# Temperature_Sensors.net
KiCad netlist of a schematic drawn in Altium Designer
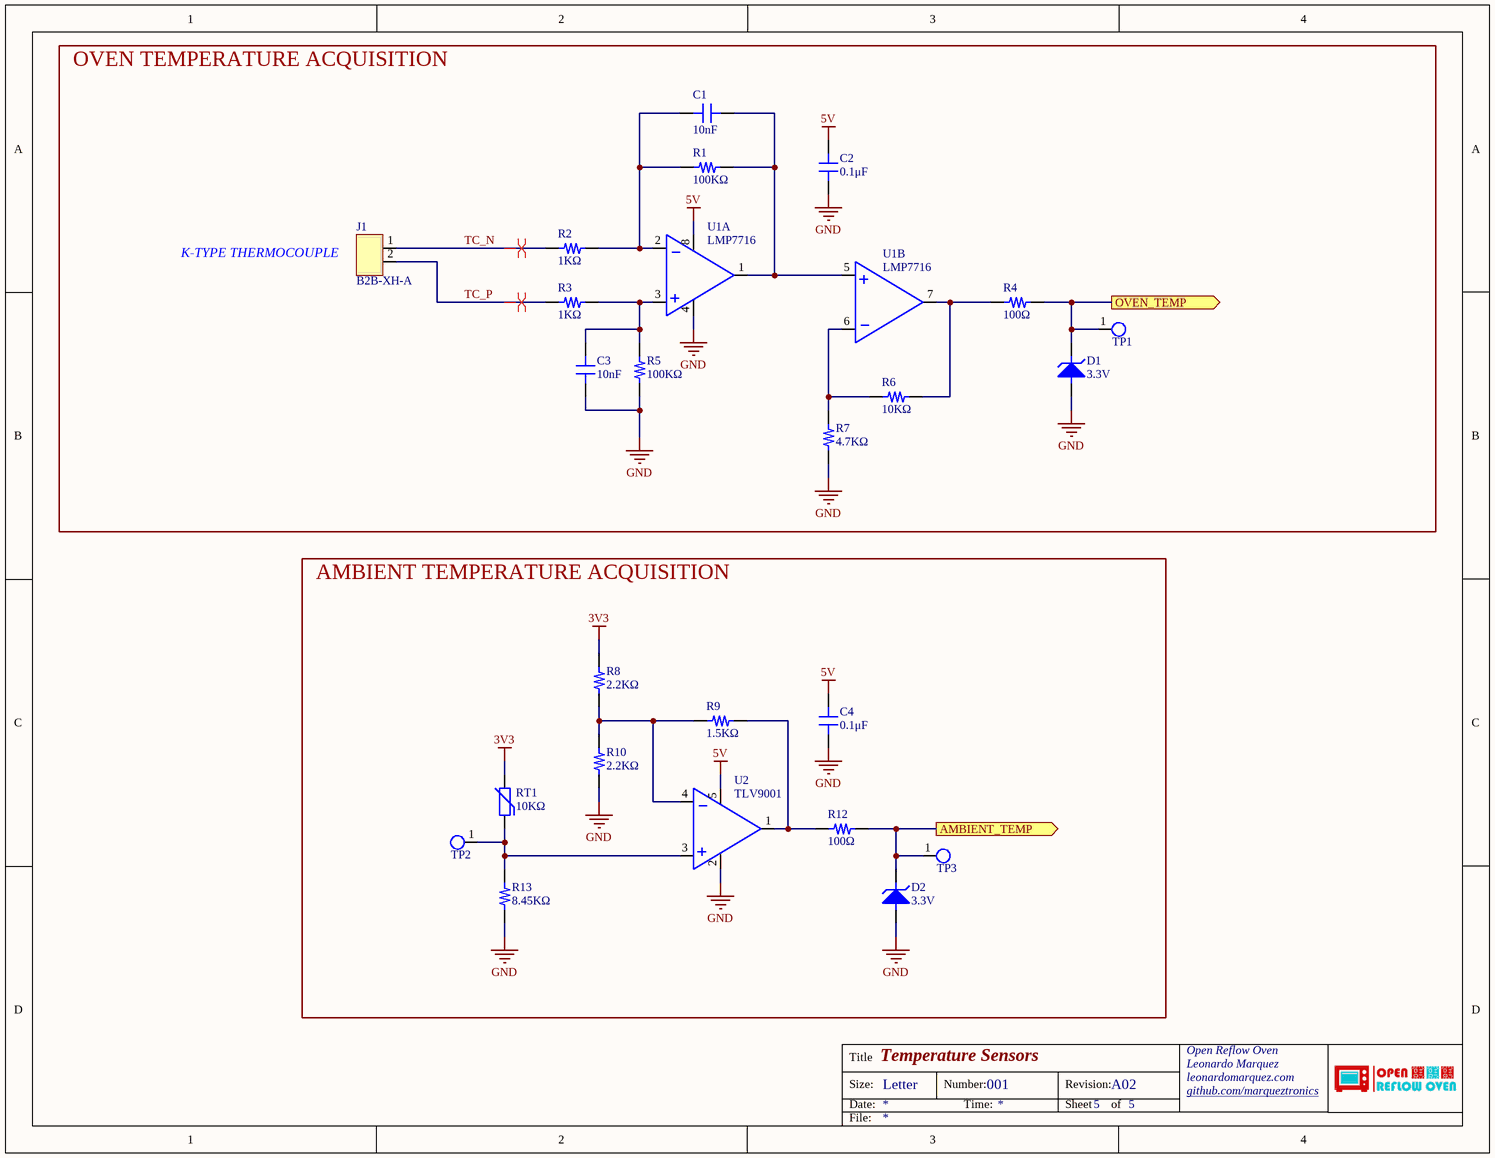
[diagram p0: Temperature Sensors.SchDoc]

(export (version "E")
  (design (tool "Eeschema 10.0.6"))
  (components
    (comp (ref "C1")
      (value "10nF")
      (footprint "C0603")
      (description "50V 10nF X7R ±10% 0603 Multilayer Ceramic Capacitors MLCC - SMD/SMT ROHS")
      (fields
        (field (name "MANUFACTURER") "Samsung Electro-Mechanics")
        (field (name "MANUFACTURER PART NUMBER") "CL10B103KB8NNNC")
      )
      (libsource (lib "REFLOW_CONTROLLER") (part "C-10NF-50V-X7R-C0603"))
    )
    (comp (ref "C2")
      (value "0.1μF")
      (footprint "C0603")
      (description "50V 100nF X7R ±10% 0603 Multilayer Ceramic Capacitors MLCC - SMD/SMT ROHS")
      (fields
        (field (name "MANUFACTURER") "Samsung Electro-Mechanics")
        (field (name "MANUFACTURER PART NUMBER") "CL10B104KB8NNNC")
      )
      (libsource (lib "REFLOW_CONTROLLER") (part "C-0.1UF-50V-X7R-C0603"))
    )
    (comp (ref "C3")
      (value "10nF")
      (footprint "C0603")
      (description "50V 10nF X7R ±10% 0603 Multilayer Ceramic Capacitors MLCC - SMD/SMT ROHS")
      (fields
        (field (name "MANUFACTURER") "Samsung Electro-Mechanics")
        (field (name "MANUFACTURER PART NUMBER") "CL10B103KB8NNNC")
      )
      (libsource (lib "REFLOW_CONTROLLER") (part "C-10NF-50V-X7R-C0603"))
    )
    (comp (ref "C4")
      (value "0.1μF")
      (footprint "C0603")
      (description "50V 100nF X7R ±10% 0603 Multilayer Ceramic Capacitors MLCC - SMD/SMT ROHS")
      (fields
        (field (name "MANUFACTURER") "Samsung Electro-Mechanics")
        (field (name "MANUFACTURER PART NUMBER") "CL10B104KB8NNNC")
      )
      (libsource (lib "REFLOW_CONTROLLER") (part "C-0.1UF-50V-X7R-C0603"))
    )
    (comp (ref "D1")
      (value "3.3V")
      (footprint "SOD-323")
      (description "Single 3.32V~3.53V 400mW 3.3V SOD-323 Zener Diodes ROHS")
      (fields
        (field (name "MANUFACTURER") "Nexperia")
        (field (name "MANUFACTURER PART NUMBER") "PDZ3.3B,115")
      )
      (libsource (lib "REFLOW_CONTROLLER") (part "D-ZENER-3.3V-SOD-323"))
    )
    (comp (ref "D2")
      (value "3.3V")
      (footprint "SOD-323")
      (description "Single 3.32V~3.53V 400mW 3.3V SOD-323 Zener Diodes ROHS")
      (fields
        (field (name "MANUFACTURER") "Nexperia")
        (field (name "MANUFACTURER PART NUMBER") "PDZ3.3B,115")
      )
      (libsource (lib "REFLOW_CONTROLLER") (part "D-ZENER-3.3V-SOD-323"))
    )
    (comp (ref "J1")
      (value "B2B-XH-A")
      (footprint "B2B-XH-A")
      (description "1x2P 2P XH 1 2.5mm 2 Brass Plugin,P=2.5mm Wire To Board Connector ROHS")
      (fields
        (field (name "MANUFACTURER") "JST")
        (field (name "MANUFACTURER PART NUMBER") "B2B-XH-A(LF)(SN)")
      )
      (libsource (lib "REFLOW_CONTROLLER") (part "J-2P-2.5MM-B2B-XH-A"))
    )
    (comp (ref "R1")
      (value "100KΩ")
      (footprint "R0603")
      (description "100mW Thick Film Resistors 75V ±100ppm/℃ ±1% 100kΩ 0603 Chip Resistor - Surface Mount ROHS")
      (fields
        (field (name "MANUFACTURER") "Yageo")
        (field (name "MANUFACTURER PART NUMBER") "RC0603FR-07100KL")
      )
      (libsource (lib "REFLOW_CONTROLLER") (part "R-100K-1/10W-R0603"))
    )
    (comp (ref "R2")
      (value "1KΩ")
      (footprint "R0603")
      (description "100mW Thick Film Resistors 75V ±100ppm/℃ ±1% 1kΩ 0603 Chip Resistor - Surface Mount ROHS")
      (fields
        (field (name "MANUFACTURER") "Yageo")
        (field (name "MANUFACTURER PART NUMBER") "RC0603FR-071KL")
      )
      (libsource (lib "REFLOW_CONTROLLER") (part "R-1K-1/10W-R0603"))
    )
    (comp (ref "R3")
      (value "1KΩ")
      (footprint "R0603")
      (description "100mW Thick Film Resistors 75V ±100ppm/℃ ±1% 1kΩ 0603 Chip Resistor - Surface Mount ROHS")
      (fields
        (field (name "MANUFACTURER") "Yageo")
        (field (name "MANUFACTURER PART NUMBER") "RC0603FR-071KL")
      )
      (libsource (lib "REFLOW_CONTROLLER") (part "R-1K-1/10W-R0603"))
    )
    (comp (ref "R4")
      (value "100Ω")
      (footprint "R0603")
      (description "100mW Thick Film Resistors 75V ±100ppm/℃ ±1% 100Ω 0603 Chip Resistor - Surface Mount ROHS")
      (fields
        (field (name "MANUFACTURER") "Yageo")
        (field (name "MANUFACTURER PART NUMBER") "RC0603FR-07100RL")
      )
      (libsource (lib "REFLOW_CONTROLLER") (part "R-100-1/10W-R0603"))
    )
    (comp (ref "R5")
      (value "100KΩ")
      (footprint "R0603")
      (description "100mW Thick Film Resistors 75V ±100ppm/℃ ±1% 100kΩ 0603 Chip Resistor - Surface Mount ROHS")
      (fields
        (field (name "MANUFACTURER") "Yageo")
        (field (name "MANUFACTURER PART NUMBER") "RC0603FR-07100KL")
      )
      (libsource (lib "REFLOW_CONTROLLER") (part "R-100K-1/10W-R0603"))
    )
    (comp (ref "R6")
      (value "10KΩ")
      (footprint "R0603")
      (description "100mW Thick Film Resistors 75V ±100ppm/℃ ±1% 10kΩ 0603 Chip Resistor - Surface Mount ROHS")
      (fields
        (field (name "MANUFACTURER") "Yageo")
        (field (name "MANUFACTURER PART NUMBER") "RC0603FR-0710KL")
      )
      (libsource (lib "REFLOW_CONTROLLER") (part "R-10K-1/10W-R0603"))
    )
    (comp (ref "R7")
      (value "4.7KΩ")
      (footprint "R0603")
      (description "100mW Thick Film Resistors 75V ±100ppm/℃ ±1% 4.7kΩ 0603 Chip Resistor - Surface Mount ROHS")
      (fields
        (field (name "MANUFACTURER") "Yageo")
        (field (name "MANUFACTURER PART NUMBER") "RC0603FR-074K7L")
      )
      (libsource (lib "REFLOW_CONTROLLER") (part "R-4.7K-1/10W-R0603"))
    )
    (comp (ref "R8")
      (value "2.2KΩ")
      (footprint "R0603")
      (description "100mW Thick Film Resistors 75V ±100ppm/℃ ±1% 2.2kΩ 0603 Chip Resistor - Surface Mount ROHS")
      (fields
        (field (name "MANUFACTURER") "Yageo")
        (field (name "MANUFACTURER PART NUMBER") "RC0603FR-072K2L")
      )
      (libsource (lib "REFLOW_CONTROLLER") (part "R-2.2K-1/10W-R0603"))
    )
    (comp (ref "R9")
      (value "1.5KΩ")
      (footprint "R0603")
      (description "100mW Thick Film Resistors 75V ±100ppm/℃ ±1% 1.5kΩ 0603 Chip Resistor - Surface Mount ROHS")
      (fields
        (field (name "MANUFACTURER") "Yageo")
        (field (name "MANUFACTURER PART NUMBER") "RC0603FR-071K5L")
      )
      (libsource (lib "REFLOW_CONTROLLER") (part "R-1.5K-1/10W-R0603"))
    )
    (comp (ref "R10")
      (value "2.2KΩ")
      (footprint "R0603")
      (description "100mW Thick Film Resistors 75V ±100ppm/℃ ±1% 2.2kΩ 0603 Chip Resistor - Surface Mount ROHS")
      (fields
        (field (name "MANUFACTURER") "Yageo")
        (field (name "MANUFACTURER PART NUMBER") "RC0603FR-072K2L")
      )
      (libsource (lib "REFLOW_CONTROLLER") (part "R-2.2K-1/10W-R0603"))
    )
    (comp (ref "R12")
      (value "100Ω")
      (footprint "R0603")
      (description "100mW Thick Film Resistors 75V ±100ppm/℃ ±1% 100Ω 0603 Chip Resistor - Surface Mount ROHS")
      (fields
        (field (name "MANUFACTURER") "Yageo")
        (field (name "MANUFACTURER PART NUMBER") "RC0603FR-07100RL")
      )
      (libsource (lib "REFLOW_CONTROLLER") (part "R-100-1/10W-R0603"))
    )
    (comp (ref "R13")
      (value "8.45KΩ")
      (footprint "R0603")
      (description "100mW Thick Film Resistors 75V ±100ppm/℃ ±1% 8.45kΩ 0603 Chip Resistor - Surface Mount ROHS")
      (fields
        (field (name "MANUFACTURER") "Yageo")
        (field (name "MANUFACTURER PART NUMBER") "RC0603FR-078K45L")
      )
      (libsource (lib "REFLOW_CONTROLLER") (part "R-8.45K-1/10W-R0603"))
    )
    (comp (ref "RT1")
      (value "10KΩ")
      (footprint "RT0603")
      (description "10kΩ 330uA 100mW ±1% 3950K ±1% 0603 NTC Thermistors ROHS")
      (fields
        (field (name "MANUFACTURER") "Sunlord")
        (field (name "MANUFACTURER PART NUMBER") "SDNT1608X103F3950FTF")
      )
      (libsource (lib "REFLOW_CONTROLLER") (part "RT-10K-NTC-RT0603"))
    )
    (comp (ref "TP1")
      (value "TP-1MM-ROUND")
      (footprint "TP-1MM-ROUND")
      (description "Round Test Point 1mm Dia")
      (libsource (lib "REFLOW_CONTROLLER") (part "TP-1MM-ROUND"))
    )
    (comp (ref "TP2")
      (value "TP-1MM-ROUND")
      (footprint "TP-1MM-ROUND")
      (description "Round Test Point 1mm Dia")
      (libsource (lib "REFLOW_CONTROLLER") (part "TP-1MM-ROUND"))
    )
    (comp (ref "TP3")
      (value "TP-1MM-ROUND")
      (footprint "TP-1MM-ROUND")
      (description "Round Test Point 1mm Dia")
      (libsource (lib "REFLOW_CONTROLLER") (part "TP-1MM-ROUND"))
    )
    (comp (ref "U1")
      (value "LMP7716")
      (footprint "VSSOP-8")
      (description "17MHz 0.1pA Dual VSSOP-8 Precision OpAmps ROHS")
      (fields
        (field (name "MANUFACTURER") "Texas Instruments")
        (field (name "MANUFACTURER PART NUMBER") "LMP7716MM/NOPB")
      )
      (libsource (lib "REFLOW_CONTROLLER") (part "U-LMP7716MM/NOPB-VSSOP-8"))
    )
    (comp (ref "U2")
      (value "TLV9001")
      (footprint "SOT-23-5")
      (description "5pA Single 1MHz SOT-23-5 Operational Amplifier ROHS")
      (fields
        (field (name "MANUFACTURER") "Texas Instruments")
        (field (name "MANUFACTURER PART NUMBER") "TLV9001IDBVR")
      )
      (libsource (lib "REFLOW_CONTROLLER") (part "U-TLV9001IDBVR-SOT-23-5"))
    )
  )
  (nets
    (net (code "1") (name "/AMBIENT_TEMP") (class "Default")
      (node (ref "D2") (pin "K") (pinfunction "K_K") (pintype "passive"))
      (node (ref "R12") (pin "2") (pinfunction "2_2") (pintype "passive"))
      (node (ref "TP3") (pin "1") (pinfunction "1_1") (pintype "passive"))
    )
    (net (code "2") (name "/OVEN_TEMP") (class "Default")
      (node (ref "D1") (pin "K") (pinfunction "K_K") (pintype "passive"))
      (node (ref "R4") (pin "2") (pinfunction "2_2") (pintype "passive"))
      (node (ref "TP1") (pin "1") (pinfunction "1_1") (pintype "passive"))
    )
    (net (code "3") (name "/TC_N") (class "Default")
      (node (ref "J1") (pin "1") (pinfunction "1_1") (pintype "passive"))
      (node (ref "R2") (pin "1") (pinfunction "1_1") (pintype "passive"))
    )
    (net (code "4") (name "/TC_P") (class "Default")
      (node (ref "J1") (pin "2") (pinfunction "2_2") (pintype "passive"))
      (node (ref "R3") (pin "1") (pinfunction "1_1") (pintype "passive"))
    )
    (net (code "5") (name "3V3") (class "Default")
      (node (ref "R8") (pin "2") (pinfunction "2_2") (pintype "passive"))
      (node (ref "RT1") (pin "2") (pinfunction "2_2") (pintype "passive"))
    )
    (net (code "6") (name "5V") (class "Default")
      (node (ref "C2") (pin "2") (pinfunction "2_2") (pintype "passive"))
      (node (ref "C4") (pin "2") (pinfunction "2_2") (pintype "passive"))
      (node (ref "U1") (pin "8") (pinfunction "V+_8") (pintype "passive"))
      (node (ref "U2") (pin "5") (pinfunction "V+_5") (pintype "passive"))
    )
    (net (code "7") (name "GND") (class "Default")
      (node (ref "C2") (pin "1") (pinfunction "1_1") (pintype "passive"))
      (node (ref "C3") (pin "1") (pinfunction "1_1") (pintype "passive"))
      (node (ref "C4") (pin "1") (pinfunction "1_1") (pintype "passive"))
      (node (ref "D1") (pin "A") (pinfunction "A_A") (pintype "passive"))
      (node (ref "D2") (pin "A") (pinfunction "A_A") (pintype "passive"))
      (node (ref "R10") (pin "1") (pinfunction "1_1") (pintype "passive"))
      (node (ref "R13") (pin "1") (pinfunction "1_1") (pintype "passive"))
      (node (ref "R5") (pin "1") (pinfunction "1_1") (pintype "passive"))
      (node (ref "R7") (pin "1") (pinfunction "1_1") (pintype "passive"))
      (node (ref "U1") (pin "4") (pinfunction "V-_4") (pintype "passive"))
      (node (ref "U2") (pin "2") (pinfunction "V-_2") (pintype "passive"))
    )
    (net (code "8") (name "Net-(U1A-+IN_A)") (class "Default")
      (node (ref "C3") (pin "2") (pinfunction "2_2") (pintype "passive"))
      (node (ref "R3") (pin "2") (pinfunction "2_2") (pintype "passive"))
      (node (ref "R5") (pin "2") (pinfunction "2_2") (pintype "passive"))
      (node (ref "U1") (pin "3") (pinfunction "+IN_A_3") (pintype "passive"))
    )
    (net (code "9") (name "Net-(U1A--IN_A)") (class "Default")
      (node (ref "C1") (pin "1") (pinfunction "1_1") (pintype "passive"))
      (node (ref "R1") (pin "2") (pinfunction "2_2") (pintype "passive"))
      (node (ref "R2") (pin "2") (pinfunction "2_2") (pintype "passive"))
      (node (ref "U1") (pin "2") (pinfunction "-IN_A_2") (pintype "passive"))
    )
    (net (code "10") (name "Net-(U1A-OUT_A)") (class "Default")
      (node (ref "C1") (pin "2") (pinfunction "2_2") (pintype "passive"))
      (node (ref "R1") (pin "1") (pinfunction "1_1") (pintype "passive"))
      (node (ref "U1") (pin "1") (pinfunction "OUT_A_1") (pintype "passive"))
      (node (ref "U1") (pin "5") (pinfunction "+IN_B_5") (pintype "passive"))
    )
    (net (code "11") (name "Net-(U1B--IN_B)") (class "Default")
      (node (ref "R6") (pin "1") (pinfunction "1_1") (pintype "passive"))
      (node (ref "R7") (pin "2") (pinfunction "2_2") (pintype "passive"))
      (node (ref "U1") (pin "6") (pinfunction "-IN_B_6") (pintype "passive"))
    )
    (net (code "12") (name "Net-(U1B-OUT_B)") (class "Default")
      (node (ref "R4") (pin "1") (pinfunction "1_1") (pintype "passive"))
      (node (ref "R6") (pin "2") (pinfunction "2_2") (pintype "passive"))
      (node (ref "U1") (pin "7") (pinfunction "OUT_B_7") (pintype "passive"))
    )
    (net (code "13") (name "Net-(U2-IN+)") (class "Default")
      (node (ref "R13") (pin "2") (pinfunction "2_2") (pintype "passive"))
      (node (ref "RT1") (pin "1") (pinfunction "1_1") (pintype "passive"))
      (node (ref "TP2") (pin "1") (pinfunction "1_1") (pintype "passive"))
      (node (ref "U2") (pin "3") (pinfunction "IN+_3") (pintype "passive"))
    )
    (net (code "14") (name "Net-(U2-IN-)") (class "Default")
      (node (ref "R10") (pin "2") (pinfunction "2_2") (pintype "passive"))
      (node (ref "R8") (pin "1") (pinfunction "1_1") (pintype "passive"))
      (node (ref "R9") (pin "1") (pinfunction "1_1") (pintype "passive"))
      (node (ref "U2") (pin "4") (pinfunction "IN-_4") (pintype "passive"))
    )
    (net (code "15") (name "Net-(U2-OUT)") (class "Default")
      (node (ref "R12") (pin "1") (pinfunction "1_1") (pintype "passive"))
      (node (ref "R9") (pin "2") (pinfunction "2_2") (pintype "passive"))
      (node (ref "U2") (pin "1") (pinfunction "OUT_1") (pintype "passive"))
    )
  )
)
